# Sheet1.net
KiCad netlist of a schematic drawn in Altium Designer
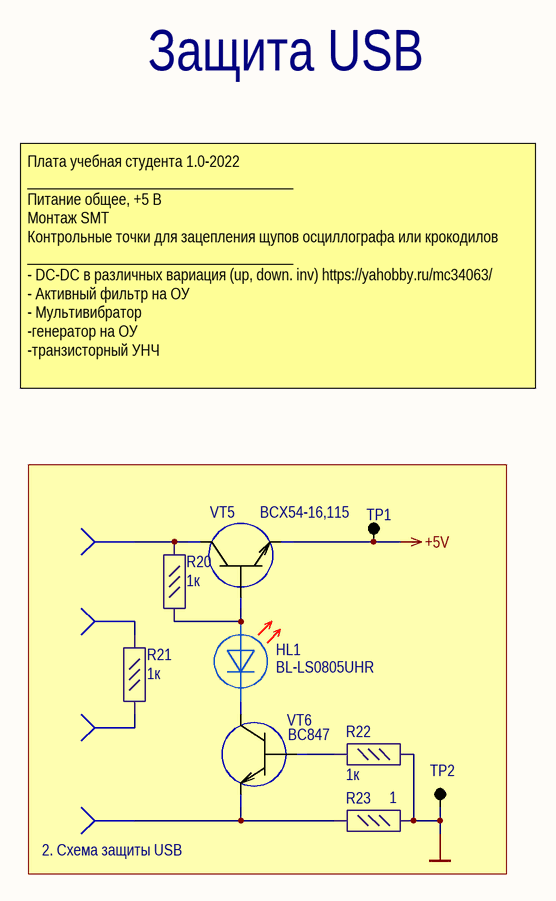
[diagram p0: Sheet1.SchDoc]

(export (version "E")
  (design (tool "Eeschema 10.0.6"))
  (components
    (comp (ref "HL1")
      (value "BL-LS0805UHR")
      (footprint "LED_0805_RED")
      (libsource (lib "4.Diodes") (part "BL-LS0805UHR"))
    )
    (comp (ref "R20")
      (value "1к")
      (footprint "R_0603")
      (description "RES SMD 10K OHM 1% 1/10W 0603")
      (fields (field (name "PART NUMBER") "CR0603-FX-1002ELF") (field (name "MANUFACTURER") "Bourns Inc."))
      (libsource (lib "Database_Lib") (part "Resistor"))
    )
    (comp (ref "R21")
      (value "1к")
      (footprint "R_0603")
      (description "RES SMD 10K OHM 1% 1/10W 0603")
      (fields (field (name "PART NUMBER") "CR0603-FX-1002ELF") (field (name "MANUFACTURER") "Bourns Inc."))
      (libsource (lib "Database_Lib") (part "Resistor"))
    )
    (comp (ref "R22")
      (value "1к")
      (footprint "R_0603")
      (description "RES SMD 10K OHM 1% 1/10W 0603")
      (fields (field (name "PART NUMBER") "CR0603-FX-1002ELF") (field (name "MANUFACTURER") "Bourns Inc."))
      (libsource (lib "Database_Lib") (part "Resistor"))
    )
    (comp (ref "R23")
      (value "1")
      (footprint "R_0603")
      (description "RES SMD 10K OHM 1% 1/10W 0603")
      (fields (field (name "PART NUMBER") "CR0603-FX-1002ELF") (field (name "MANUFACTURER") "Bourns Inc."))
      (libsource (lib "Database_Lib") (part "Resistor"))
    )
    (comp (ref "TP1")
      (value "Test_Point_1")
      (footprint "Test_point")
      (libsource (lib "7.Connectors") (part "Test_Point_1"))
    )
    (comp (ref "TP2")
      (value "Test_Point_1")
      (footprint "Test_point")
      (libsource (lib "7.Connectors") (part "Test_Point_1"))
    )
    (comp (ref "VT5")
      (value "BCX54-16,115")
      (footprint "SOT89")
      (libsource (lib "5.Transistors") (part "BCX54-16,115"))
    )
    (comp (ref "VT6") (value "BC847") (footprint "SOT23") (libsource (lib "5.Transistors") (part "BC847")))
    (comp (ref "X1")
      (value "X")
      (footprint "KT_1")
      (description "Контактная площадка")
      (libsource (lib "7.Connectors") (part "X"))
    )
    (comp (ref "X2")
      (value "X")
      (footprint "KT_1")
      (description "Контактная площадка")
      (libsource (lib "7.Connectors") (part "X"))
    )
    (comp (ref "X3")
      (value "X")
      (footprint "KT_1")
      (description "Контактная площадка")
      (libsource (lib "7.Connectors") (part "X"))
    )
    (comp (ref "X4")
      (value "X")
      (footprint "KT_1")
      (description "Контактная площадка")
      (libsource (lib "7.Connectors") (part "X"))
    )
  )
  (nets
    (net (code "1") (name "+5V") (class "Default")
      (node (ref "TP1") (pin "1") (pinfunction "1_1") (pintype "passive"))
      (node (ref "VT5") (pin "3") (pinfunction "E_3") (pintype "passive"))
    )
    (net (code "2") (name "GND") (class "Default")
      (node (ref "R22") (pin "2") (pinfunction "2_2") (pintype "passive"))
      (node (ref "R23") (pin "2") (pinfunction "2_2") (pintype "passive"))
      (node (ref "TP2") (pin "1") (pinfunction "1_1") (pintype "passive"))
    )
    (net (code "3") (name "Net-(R21-Pad1)") (class "Default")
      (node (ref "R21") (pin "1") (pinfunction "1_1") (pintype "passive"))
      (node (ref "X2") (pin "1") (pinfunction "1_1") (pintype "passive"))
    )
    (net (code "4") (name "Net-(R21-Pad2)") (class "Default")
      (node (ref "R21") (pin "2") (pinfunction "2_2") (pintype "passive"))
      (node (ref "X3") (pin "1") (pinfunction "1_1") (pintype "passive"))
    )
    (net (code "5") (name "Net-(VT5-B)") (class "Default")
      (node (ref "HL1") (pin "1") (pinfunction "1_1") (pintype "passive"))
      (node (ref "R20") (pin "2") (pinfunction "2_2") (pintype "passive"))
      (node (ref "VT5") (pin "1") (pinfunction "B_1") (pintype "passive"))
    )
    (net (code "6") (name "Net-(VT5-C)") (class "Default")
      (node (ref "R20") (pin "1") (pinfunction "1_1") (pintype "passive"))
      (node (ref "VT5") (pin "2") (pinfunction "C_2") (pintype "passive"))
      (node (ref "X1") (pin "1") (pinfunction "1_1") (pintype "passive"))
    )
    (net (code "7") (name "Net-(VT6-B)") (class "Default")
      (node (ref "R22") (pin "1") (pinfunction "1_1") (pintype "passive"))
      (node (ref "VT6") (pin "1") (pinfunction "B_1") (pintype "passive"))
    )
    (net (code "8") (name "Net-(VT6-C)") (class "Default")
      (node (ref "HL1") (pin "2") (pinfunction "2_2") (pintype "passive"))
      (node (ref "VT6") (pin "3") (pinfunction "C_3") (pintype "passive"))
    )
    (net (code "9") (name "Net-(VT6-E)") (class "Default")
      (node (ref "R23") (pin "1") (pinfunction "1_1") (pintype "passive"))
      (node (ref "VT6") (pin "2") (pinfunction "E_2") (pintype "passive"))
      (node (ref "X4") (pin "1") (pinfunction "1_1") (pintype "passive"))
    )
  )
)
